# PGA-103_LNA_Mod2.net
KiCad netlist of a schematic drawn in EAGLE
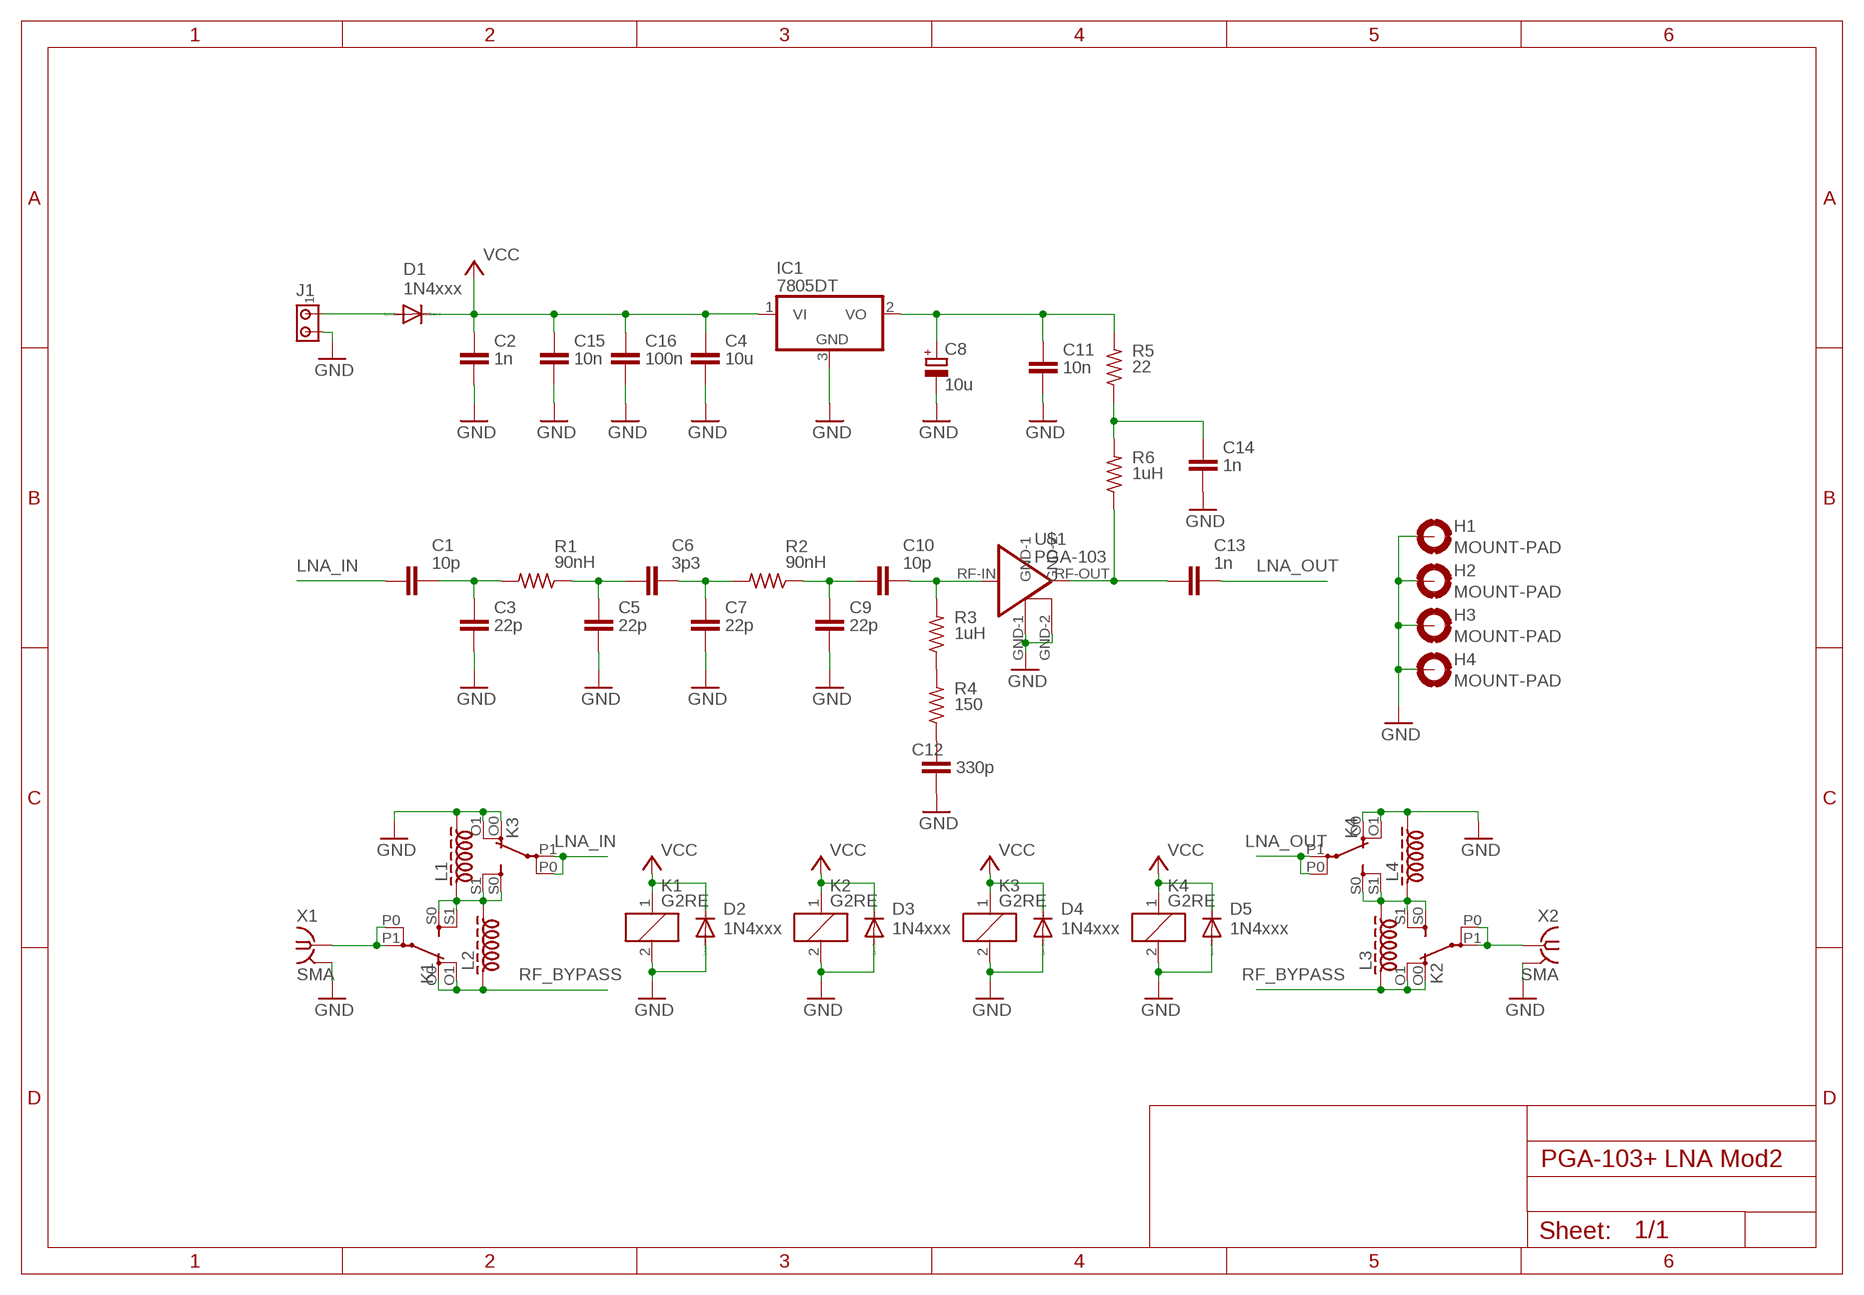
[diagram p0: schematic, sheet 1]

(export (version "E")
  (design (tool "Eeschema 10.0.6"))
  (components
    (comp (ref "C1")
      (value "10p")
      (footprint "eagle-import:C1206")
      (libsource (lib "eagle-import") (part "C-EUC1206"))
    )
    (comp (ref "C2")
      (value "1n")
      (footprint "eagle-import:C1206")
      (libsource (lib "eagle-import") (part "C-EUC1206"))
    )
    (comp (ref "C3")
      (value "22p")
      (footprint "eagle-import:C1206")
      (libsource (lib "eagle-import") (part "C-EUC1206"))
    )
    (comp (ref "C4")
      (value "10u")
      (footprint "eagle-import:C1206")
      (libsource (lib "eagle-import") (part "C-EUC1206"))
    )
    (comp (ref "C5")
      (value "22p")
      (footprint "eagle-import:C1206")
      (libsource (lib "eagle-import") (part "C-EUC1206"))
    )
    (comp (ref "C6")
      (value "3p3")
      (footprint "eagle-import:C1206")
      (libsource (lib "eagle-import") (part "C-EUC1206"))
    )
    (comp (ref "C7")
      (value "22p")
      (footprint "eagle-import:C1206")
      (libsource (lib "eagle-import") (part "C-EUC1206"))
    )
    (comp (ref "C8")
      (value "10u")
      (footprint "eagle-import:B_3528-21R")
      (libsource (lib "eagle-import") (part "CPOL-EUB/3528-21R"))
    )
    (comp (ref "C9")
      (value "22p")
      (footprint "eagle-import:C1206")
      (libsource (lib "eagle-import") (part "C-EUC1206"))
    )
    (comp (ref "C10")
      (value "10p")
      (footprint "eagle-import:C1206")
      (libsource (lib "eagle-import") (part "C-EUC1206"))
    )
    (comp (ref "C11")
      (value "10n")
      (footprint "eagle-import:C1206")
      (libsource (lib "eagle-import") (part "C-EUC1206"))
    )
    (comp (ref "C12")
      (value "330p")
      (footprint "eagle-import:C1206")
      (libsource (lib "eagle-import") (part "C-EUC1206"))
    )
    (comp (ref "C13")
      (value "1n")
      (footprint "eagle-import:C1206")
      (libsource (lib "eagle-import") (part "C-EUC1206"))
    )
    (comp (ref "C14")
      (value "1n")
      (footprint "eagle-import:C1206")
      (libsource (lib "eagle-import") (part "C-EUC1206"))
    )
    (comp (ref "C15")
      (value "10n")
      (footprint "eagle-import:C1206")
      (libsource (lib "eagle-import") (part "C-EUC1206"))
    )
    (comp (ref "C16")
      (value "100n")
      (footprint "eagle-import:C1206")
      (libsource (lib "eagle-import") (part "C-EUC1206"))
    )
    (comp (ref "D1")
      (value "1N4xxx")
      (footprint "eagle-import:DO35-7")
      (libsource (lib "eagle-import") (part "1N4148DO35-7"))
    )
    (comp (ref "D2")
      (value "1N4xxx")
      (footprint "eagle-import:DO35-7")
      (libsource (lib "eagle-import") (part "1N4148DO35-7"))
    )
    (comp (ref "D3")
      (value "1N4xxx")
      (footprint "eagle-import:DO35-7")
      (libsource (lib "eagle-import") (part "1N4148DO35-7"))
    )
    (comp (ref "D4")
      (value "1N4xxx")
      (footprint "eagle-import:DO35-7")
      (libsource (lib "eagle-import") (part "1N4148DO35-7"))
    )
    (comp (ref "D5")
      (value "1N4xxx")
      (footprint "eagle-import:DO35-7")
      (libsource (lib "eagle-import") (part "1N4148DO35-7"))
    )
    (comp (ref "H1")
      (value "MOUNT-PAD")
      (footprint "eagle-import:2,8-PAD")
      (libsource (lib "eagle-import") (part "MOUNT-PAD-ROUND2.8"))
    )
    (comp (ref "H2")
      (value "MOUNT-PAD")
      (footprint "eagle-import:2,8-PAD")
      (libsource (lib "eagle-import") (part "MOUNT-PAD-ROUND2.8"))
    )
    (comp (ref "H3")
      (value "MOUNT-PAD")
      (footprint "eagle-import:2,8-PAD")
      (libsource (lib "eagle-import") (part "MOUNT-PAD-ROUND2.8"))
    )
    (comp (ref "H4")
      (value "MOUNT-PAD")
      (footprint "eagle-import:2,8-PAD")
      (libsource (lib "eagle-import") (part "MOUNT-PAD-ROUND2.8"))
    )
    (comp (ref "IC1")
      (value "7805DT")
      (footprint "eagle-import:TO252")
      (libsource (lib "eagle-import") (part "78DT05"))
    )
    (comp (ref "J1")
      (value "MTA02-156")
      (footprint "eagle-import:1X2MTA")
      (libsource (lib "eagle-import") (part "MTA02-156"))
    )
    (comp (ref "K1")
      (value "G2RE")
      (footprint "eagle-import:G2RE")
      (libsource (lib "eagle-import") (part "G2RE"))
    )
    (comp (ref "K2")
      (value "G2RE")
      (footprint "eagle-import:G2RE")
      (libsource (lib "eagle-import") (part "G2RE"))
    )
    (comp (ref "K3")
      (value "G2RE")
      (footprint "eagle-import:G2RE")
      (libsource (lib "eagle-import") (part "G2RE"))
    )
    (comp (ref "K4")
      (value "G2RE")
      (footprint "eagle-import:G2RE")
      (libsource (lib "eagle-import") (part "G2RE"))
    )
    (comp (ref "L1")
      (value "Z28/70CW")
      (footprint "eagle-import:Z28_7")
      (libsource (lib "eagle-import") (part "Z?CW28/70"))
    )
    (comp (ref "L2")
      (value "Z28/70CW")
      (footprint "eagle-import:Z28_7")
      (libsource (lib "eagle-import") (part "Z?CW28/70"))
    )
    (comp (ref "L3")
      (value "Z28/70CW")
      (footprint "eagle-import:Z28_7")
      (libsource (lib "eagle-import") (part "Z?CW28/70"))
    )
    (comp (ref "L4")
      (value "Z28/70CW")
      (footprint "eagle-import:Z28_7")
      (libsource (lib "eagle-import") (part "Z?CW28/70"))
    )
    (comp (ref "R1")
      (value "90nH")
      (footprint "eagle-import:M1206")
      (libsource (lib "eagle-import") (part "R-US_M1206"))
    )
    (comp (ref "R2")
      (value "90nH")
      (footprint "eagle-import:M1206")
      (libsource (lib "eagle-import") (part "R-US_M1206"))
    )
    (comp (ref "R3")
      (value "1uH")
      (footprint "eagle-import:M1206")
      (libsource (lib "eagle-import") (part "R-US_M1206"))
    )
    (comp (ref "R4")
      (value "150")
      (footprint "eagle-import:M1206")
      (libsource (lib "eagle-import") (part "R-US_M1206"))
    )
    (comp (ref "R5")
      (value "22")
      (footprint "eagle-import:M1206")
      (libsource (lib "eagle-import") (part "R-US_M1206"))
    )
    (comp (ref "R6")
      (value "1uH")
      (footprint "eagle-import:M1206")
      (libsource (lib "eagle-import") (part "R-US_M1206"))
    )
    (comp (ref "U$1")
      (value "PGA-103")
      (footprint "eagle-import:DF782")
      (libsource (lib "eagle-import") (part "PGA-103"))
    )
    (comp (ref "X1")
      (value "SMA")
      (footprint "eagle-import:J502-ND-142-0701-851_861")
      (fields (field (name "MF") "JOHNSON COMPONENTS") (field (name "MPN") "142-0701-851"))
      (libsource (lib "eagle-import") (part "SMA-142-0701-851/861"))
    )
    (comp (ref "X2")
      (value "SMA")
      (footprint "eagle-import:J502-ND-142-0701-851_861")
      (fields (field (name "MF") "JOHNSON COMPONENTS") (field (name "MPN") "142-0701-851"))
      (libsource (lib "eagle-import") (part "SMA-142-0701-851/861"))
    )
  )
  (nets
    (net (code "1") (name "/LNA_IN") (class "Default")
      (node (ref "C1") (pin "1") (pinfunction "1_1") (pintype "passive"))
      (node (ref "K3") (pin "P0") (pinfunction "P_P0") (pintype "passive"))
      (node (ref "K3") (pin "P1") (pinfunction "P_P1") (pintype "passive"))
    )
    (net (code "2") (name "/LNA_OUT") (class "Default")
      (node (ref "C13") (pin "2") (pinfunction "2_2") (pintype "passive"))
      (node (ref "K4") (pin "P0") (pinfunction "P_P0") (pintype "passive"))
      (node (ref "K4") (pin "P1") (pinfunction "P_P1") (pintype "passive"))
    )
    (net (code "3") (name "/RF_BYPASS") (class "Default")
      (node (ref "K1") (pin "O0") (pinfunction "O_O0") (pintype "passive"))
      (node (ref "K1") (pin "O1") (pinfunction "O_O1") (pintype "passive"))
      (node (ref "K2") (pin "O0") (pinfunction "O_O0") (pintype "passive"))
      (node (ref "K2") (pin "O1") (pinfunction "O_O1") (pintype "passive"))
      (node (ref "L2") (pin "1") (pinfunction "1_1") (pintype "passive"))
      (node (ref "L3") (pin "1") (pinfunction "1_1") (pintype "passive"))
    )
    (net (code "4") (name "GND") (class "Default")
      (node (ref "C11") (pin "2") (pinfunction "2_2") (pintype "passive"))
      (node (ref "C12") (pin "1") (pinfunction "1_1") (pintype "passive"))
      (node (ref "C14") (pin "1") (pinfunction "1_1") (pintype "passive"))
      (node (ref "C15") (pin "2") (pinfunction "2_2") (pintype "passive"))
      (node (ref "C16") (pin "2") (pinfunction "2_2") (pintype "passive"))
      (node (ref "C2") (pin "2") (pinfunction "2_2") (pintype "passive"))
      (node (ref "C3") (pin "1") (pinfunction "1_1") (pintype "passive"))
      (node (ref "C4") (pin "2") (pinfunction "2_2") (pintype "passive"))
      (node (ref "C5") (pin "1") (pinfunction "1_1") (pintype "passive"))
      (node (ref "C7") (pin "1") (pinfunction "1_1") (pintype "passive"))
      (node (ref "C8") (pin "-") (pinfunction "-_-") (pintype "passive"))
      (node (ref "C9") (pin "1") (pinfunction "1_1") (pintype "passive"))
      (node (ref "D2") (pin "A") (pinfunction "A_A") (pintype "passive"))
      (node (ref "D3") (pin "A") (pinfunction "A_A") (pintype "passive"))
      (node (ref "D4") (pin "A") (pinfunction "A_A") (pintype "passive"))
      (node (ref "D5") (pin "A") (pinfunction "A_A") (pintype "passive"))
      (node (ref "H1") (pin "B2,8") (pinfunction "MOUNT_B2,8") (pintype "passive"))
      (node (ref "H2") (pin "B2,8") (pinfunction "MOUNT_B2,8") (pintype "passive"))
      (node (ref "H3") (pin "B2,8") (pinfunction "MOUNT_B2,8") (pintype "passive"))
      (node (ref "H4") (pin "B2,8") (pinfunction "MOUNT_B2,8") (pintype "passive"))
      (node (ref "IC1") (pin "3") (pinfunction "GND_3") (pintype "passive"))
      (node (ref "J1") (pin "2") (pinfunction "2_2") (pintype "passive"))
      (node (ref "K1") (pin "2") (pinfunction "2_2") (pintype "passive"))
      (node (ref "K2") (pin "2") (pinfunction "2_2") (pintype "passive"))
      (node (ref "K3") (pin "2") (pinfunction "2_2") (pintype "passive"))
      (node (ref "K3") (pin "O0") (pinfunction "O_O0") (pintype "passive"))
      (node (ref "K3") (pin "O1") (pinfunction "O_O1") (pintype "passive"))
      (node (ref "K4") (pin "2") (pinfunction "2_2") (pintype "passive"))
      (node (ref "K4") (pin "O0") (pinfunction "O_O0") (pintype "passive"))
      (node (ref "K4") (pin "O1") (pinfunction "O_O1") (pintype "passive"))
      (node (ref "L1") (pin "2") (pinfunction "2_2") (pintype "passive"))
      (node (ref "L4") (pin "2") (pinfunction "2_2") (pintype "passive"))
      (node (ref "U$1") (pin "GND-1") (pinfunction "GND-1_GND-1") (pintype "power_in"))
      (node (ref "U$1") (pin "GND-2") (pinfunction "GND-2_GND-2") (pintype "power_in"))
      (node (ref "X1") (pin "G@1") (pinfunction "2_G@1") (pintype "passive"))
      (node (ref "X1") (pin "G@2") (pinfunction "2_G@2") (pintype "passive"))
      (node (ref "X1") (pin "G@3") (pinfunction "2_G@3") (pintype "passive"))
      (node (ref "X1") (pin "G@4") (pinfunction "2_G@4") (pintype "passive"))
      (node (ref "X2") (pin "G@1") (pinfunction "2_G@1") (pintype "passive"))
      (node (ref "X2") (pin "G@2") (pinfunction "2_G@2") (pintype "passive"))
      (node (ref "X2") (pin "G@3") (pinfunction "2_G@3") (pintype "passive"))
      (node (ref "X2") (pin "G@4") (pinfunction "2_G@4") (pintype "passive"))
    )
    (net (code "5") (name "Net-(C1-Pad2)") (class "Default")
      (node (ref "C1") (pin "2") (pinfunction "2_2") (pintype "passive"))
      (node (ref "C3") (pin "2") (pinfunction "2_2") (pintype "passive"))
      (node (ref "R1") (pin "2") (pinfunction "2_2") (pintype "passive"))
    )
    (net (code "6") (name "Net-(C5-Pad2)") (class "Default")
      (node (ref "C5") (pin "2") (pinfunction "2_2") (pintype "passive"))
      (node (ref "C6") (pin "1") (pinfunction "1_1") (pintype "passive"))
      (node (ref "R1") (pin "1") (pinfunction "1_1") (pintype "passive"))
    )
    (net (code "7") (name "Net-(C6-Pad2)") (class "Default")
      (node (ref "C6") (pin "2") (pinfunction "2_2") (pintype "passive"))
      (node (ref "C7") (pin "2") (pinfunction "2_2") (pintype "passive"))
      (node (ref "R2") (pin "2") (pinfunction "2_2") (pintype "passive"))
    )
    (net (code "8") (name "Net-(C10-Pad1)") (class "Default")
      (node (ref "C10") (pin "1") (pinfunction "1_1") (pintype "passive"))
      (node (ref "C9") (pin "2") (pinfunction "2_2") (pintype "passive"))
      (node (ref "R2") (pin "1") (pinfunction "1_1") (pintype "passive"))
    )
    (net (code "9") (name "Net-(C10-Pad2)") (class "Default")
      (node (ref "C10") (pin "2") (pinfunction "2_2") (pintype "passive"))
      (node (ref "R3") (pin "2") (pinfunction "2_2") (pintype "passive"))
      (node (ref "U$1") (pin "RF-IN") (pinfunction "RF-IN_RF-IN") (pintype "input"))
    )
    (net (code "10") (name "Net-(C12-Pad2)") (class "Default")
      (node (ref "C12") (pin "2") (pinfunction "2_2") (pintype "passive"))
      (node (ref "R4") (pin "1") (pinfunction "1_1") (pintype "passive"))
    )
    (net (code "11") (name "Net-(C13-Pad1)") (class "Default")
      (node (ref "C13") (pin "1") (pinfunction "1_1") (pintype "passive"))
      (node (ref "R6") (pin "1") (pinfunction "1_1") (pintype "passive"))
      (node (ref "U$1") (pin "RF-OUT") (pinfunction "RF-OUT_RF-OUT") (pintype "output"))
    )
    (net (code "12") (name "Net-(C14-Pad2)") (class "Default")
      (node (ref "C14") (pin "2") (pinfunction "2_2") (pintype "passive"))
      (node (ref "R5") (pin "1") (pinfunction "1_1") (pintype "passive"))
      (node (ref "R6") (pin "2") (pinfunction "2_2") (pintype "passive"))
    )
    (net (code "13") (name "Net-(D1-PadA)") (class "Default")
      (node (ref "D1") (pin "A") (pinfunction "A_A") (pintype "passive"))
      (node (ref "J1") (pin "1") (pinfunction "1_1") (pintype "passive"))
    )
    (net (code "14") (name "Net-(IC1-VO)") (class "Default")
      (node (ref "C11") (pin "1") (pinfunction "1_1") (pintype "passive"))
      (node (ref "C8") (pin "+") (pinfunction "+_+") (pintype "passive"))
      (node (ref "IC1") (pin "2") (pinfunction "VO_2") (pintype "passive"))
      (node (ref "R5") (pin "2") (pinfunction "2_2") (pintype "passive"))
    )
    (net (code "15") (name "Net-(K1B-P-PadP0)") (class "Default")
      (node (ref "K1") (pin "P0") (pinfunction "P_P0") (pintype "passive"))
      (node (ref "K1") (pin "P1") (pinfunction "P_P1") (pintype "passive"))
      (node (ref "X1") (pin "1") (pinfunction "1_1") (pintype "passive"))
    )
    (net (code "16") (name "Net-(K1B-S-PadS0)") (class "Default")
      (node (ref "K1") (pin "S0") (pinfunction "S_S0") (pintype "passive"))
      (node (ref "K1") (pin "S1") (pinfunction "S_S1") (pintype "passive"))
      (node (ref "K3") (pin "S0") (pinfunction "S_S0") (pintype "passive"))
      (node (ref "K3") (pin "S1") (pinfunction "S_S1") (pintype "passive"))
      (node (ref "L1") (pin "1") (pinfunction "1_1") (pintype "passive"))
      (node (ref "L2") (pin "2") (pinfunction "2_2") (pintype "passive"))
    )
    (net (code "17") (name "Net-(K2B-P-PadP0)") (class "Default")
      (node (ref "K2") (pin "P0") (pinfunction "P_P0") (pintype "passive"))
      (node (ref "K2") (pin "P1") (pinfunction "P_P1") (pintype "passive"))
      (node (ref "X2") (pin "1") (pinfunction "1_1") (pintype "passive"))
    )
    (net (code "18") (name "Net-(K2B-S-PadS0)") (class "Default")
      (node (ref "K2") (pin "S0") (pinfunction "S_S0") (pintype "passive"))
      (node (ref "K2") (pin "S1") (pinfunction "S_S1") (pintype "passive"))
      (node (ref "K4") (pin "S0") (pinfunction "S_S0") (pintype "passive"))
      (node (ref "K4") (pin "S1") (pinfunction "S_S1") (pintype "passive"))
      (node (ref "L3") (pin "2") (pinfunction "2_2") (pintype "passive"))
      (node (ref "L4") (pin "1") (pinfunction "1_1") (pintype "passive"))
    )
    (net (code "19") (name "Net-(R3-Pad1)") (class "Default")
      (node (ref "R3") (pin "1") (pinfunction "1_1") (pintype "passive"))
      (node (ref "R4") (pin "2") (pinfunction "2_2") (pintype "passive"))
    )
    (net (code "20") (name "VCC") (class "Default")
      (node (ref "C15") (pin "1") (pinfunction "1_1") (pintype "passive"))
      (node (ref "C16") (pin "1") (pinfunction "1_1") (pintype "passive"))
      (node (ref "C2") (pin "1") (pinfunction "1_1") (pintype "passive"))
      (node (ref "C4") (pin "1") (pinfunction "1_1") (pintype "passive"))
      (node (ref "D1") (pin "C") (pinfunction "C_C") (pintype "passive"))
      (node (ref "D2") (pin "C") (pinfunction "C_C") (pintype "passive"))
      (node (ref "D3") (pin "C") (pinfunction "C_C") (pintype "passive"))
      (node (ref "D4") (pin "C") (pinfunction "C_C") (pintype "passive"))
      (node (ref "D5") (pin "C") (pinfunction "C_C") (pintype "passive"))
      (node (ref "IC1") (pin "1") (pinfunction "VI_1") (pintype "input"))
      (node (ref "K1") (pin "1") (pinfunction "1_1") (pintype "passive"))
      (node (ref "K2") (pin "1") (pinfunction "1_1") (pintype "passive"))
      (node (ref "K3") (pin "1") (pinfunction "1_1") (pintype "passive"))
      (node (ref "K4") (pin "1") (pinfunction "1_1") (pintype "passive"))
    )
  )
)
